# gacyagacya.net
KiCad netlist of a schematic drawn in EAGLE
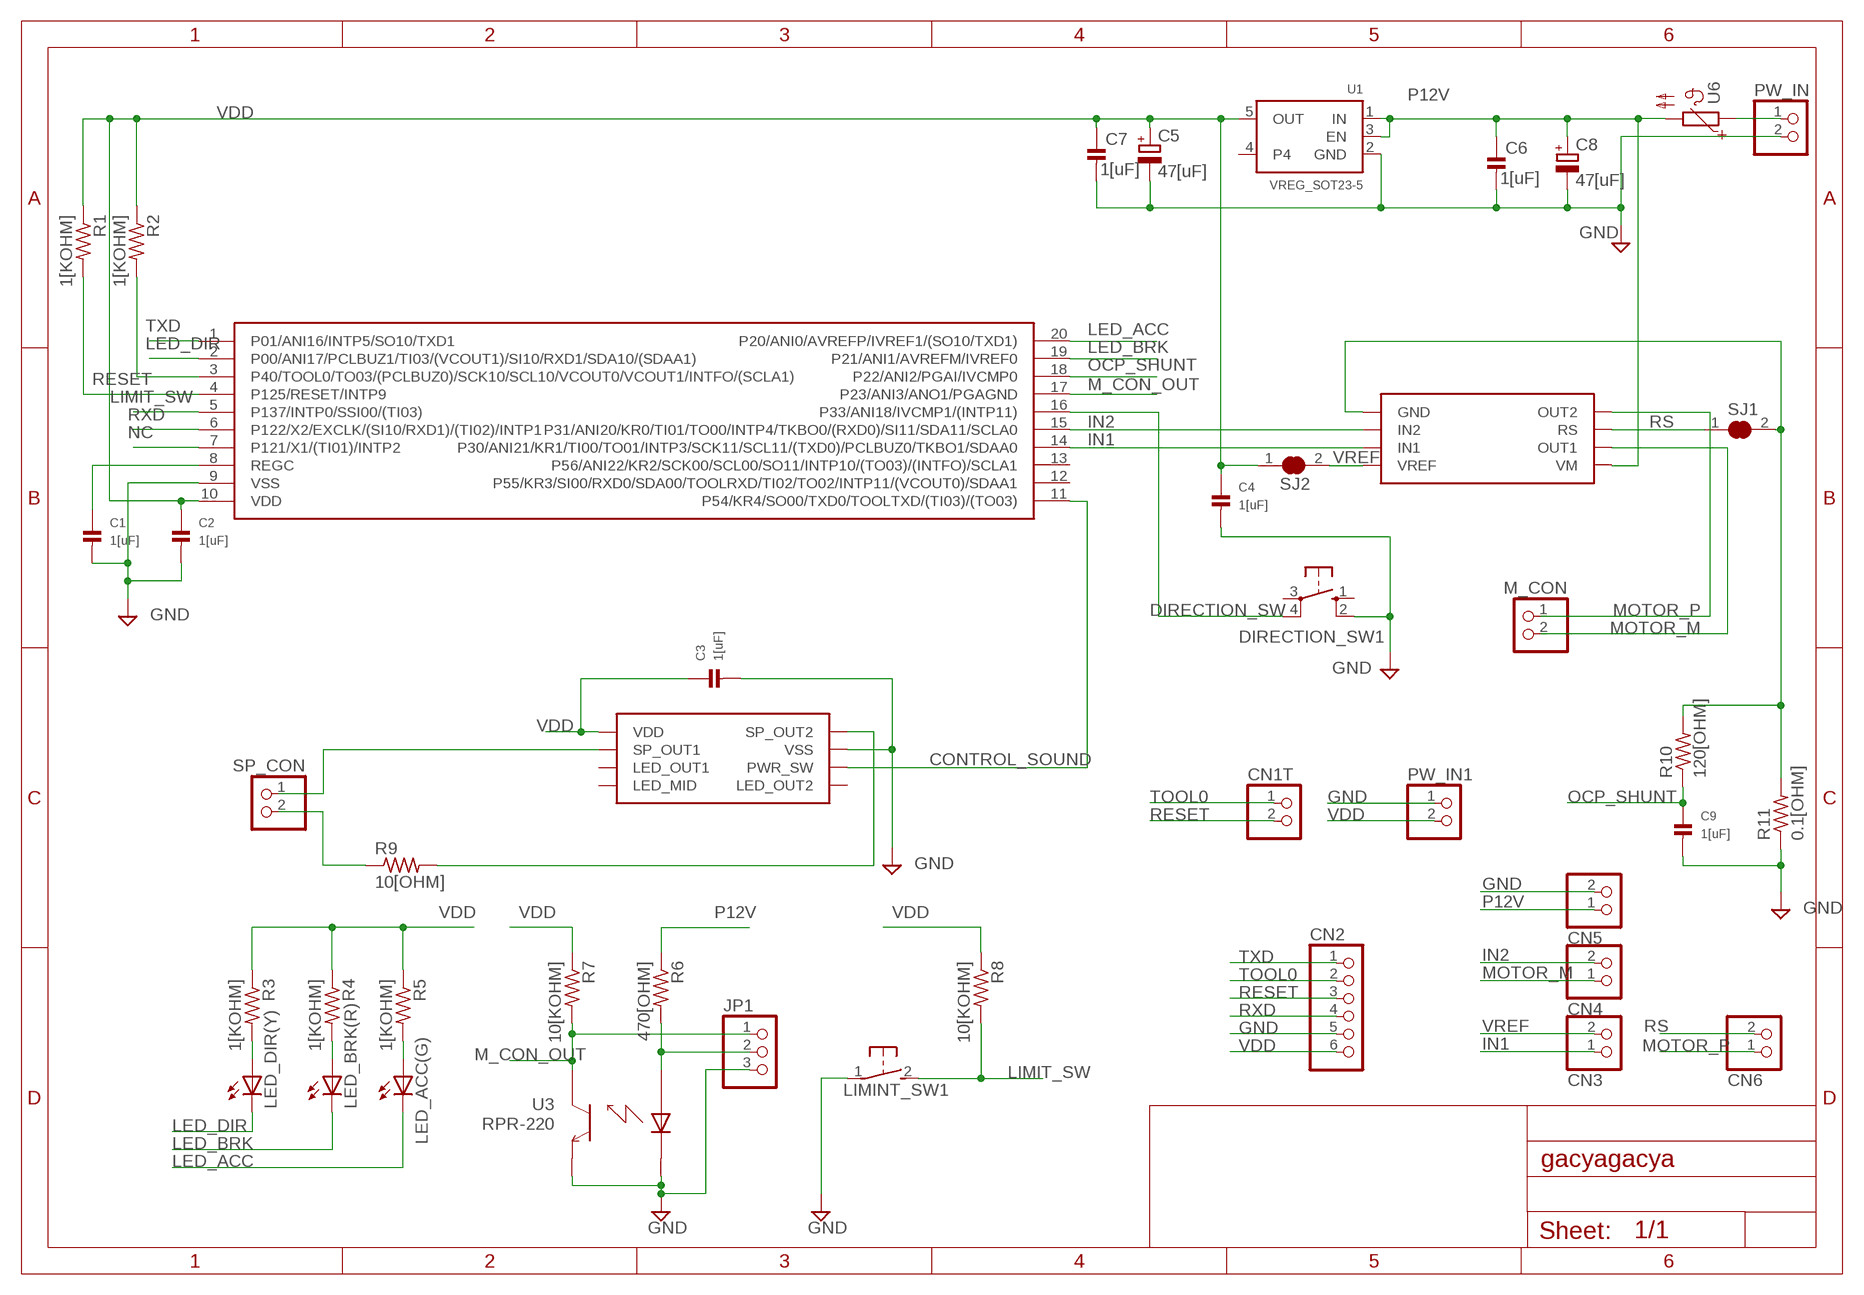
[diagram p0: schematic, sheet 1]

(export (version "E")
  (design (tool "Eeschema 10.0.6"))
  (components
    (comp (ref "C1")
      (value "1[uF]")
      (footprint "eagle-import:_0603")
      (libsource (lib "eagle-import") (part "CAP_CERAMIC_0603"))
    )
    (comp (ref "C2")
      (value "1[uF]")
      (footprint "eagle-import:_0603")
      (libsource (lib "eagle-import") (part "CAP_CERAMIC_0603"))
    )
    (comp (ref "C3")
      (value "1[uF]")
      (footprint "eagle-import:_0603")
      (libsource (lib "eagle-import") (part "CAP_CERAMIC_0603"))
    )
    (comp (ref "C4")
      (value "1[uF]")
      (footprint "eagle-import:_0603")
      (libsource (lib "eagle-import") (part "CAP_CERAMIC_0603"))
    )
    (comp (ref "C5")
      (value "47[uF]")
      (footprint "eagle-import:E1,8-4")
      (libsource (lib "eagle-import") (part "CPOL-EUE1.8-4"))
    )
    (comp (ref "C6")
      (value "1[uF]")
      (footprint "eagle-import:_0603")
      (libsource (lib "eagle-import") (part "CAP_CERAMIC_0603"))
    )
    (comp (ref "C7")
      (value "1[uF]")
      (footprint "eagle-import:_0603")
      (libsource (lib "eagle-import") (part "CAP_CERAMIC_0603"))
    )
    (comp (ref "C8")
      (value "47[uF]")
      (footprint "eagle-import:E1,8-4")
      (libsource (lib "eagle-import") (part "CPOL-EUE1.8-4"))
    )
    (comp (ref "C9")
      (value "1[uF]")
      (footprint "eagle-import:_0603")
      (libsource (lib "eagle-import") (part "CAP_CERAMIC_0603"))
    )
    (comp (ref "CN1T")
      (value "HEADER-1X2ROUND")
      (footprint "eagle-import:1X02_ROUND")
      (libsource (lib "eagle-import") (part "HEADER-1X2ROUND"))
    )
    (comp (ref "CN2")
      (value "XSR_6PIN")
      (footprint "eagle-import:XSR_6PIN")
      (libsource (lib "eagle-import") (part "XSR_6PIN"))
    )
    (comp (ref "CN3")
      (value "HEADER-1X2ROUND")
      (footprint "eagle-import:1X02_ROUND")
      (libsource (lib "eagle-import") (part "HEADER-1X2ROUND"))
    )
    (comp (ref "CN4")
      (value "HEADER-1X2ROUND")
      (footprint "eagle-import:1X02_ROUND")
      (libsource (lib "eagle-import") (part "HEADER-1X2ROUND"))
    )
    (comp (ref "CN5")
      (value "HEADER-1X2ROUND")
      (footprint "eagle-import:1X02_ROUND")
      (libsource (lib "eagle-import") (part "HEADER-1X2ROUND"))
    )
    (comp (ref "CN6")
      (value "HEADER-1X2ROUND")
      (footprint "eagle-import:1X02_ROUND")
      (libsource (lib "eagle-import") (part "HEADER-1X2ROUND"))
    )
    (comp (ref "DIRECTION_SW1")
      (value "10-XXSMD_TACT_SW")
      (footprint "eagle-import:SMD_TACT_SW")
      (libsource (lib "eagle-import") (part "10-XXSMD_TACT_SW"))
    )
    (comp (ref "JP1")
      (value "HEADER-1X3ROUND")
      (footprint "eagle-import:1X03_ROUND")
      (libsource (lib "eagle-import") (part "HEADER-1X3ROUND"))
    )
    (comp (ref "LED_ACC(G)")
      (value "LED3MM")
      (footprint "eagle-import:LED3MM")
      (libsource (lib "eagle-import") (part "LED3MM"))
    )
    (comp (ref "LED_BRK(R)")
      (value "LED3MM")
      (footprint "eagle-import:LED3MM")
      (libsource (lib "eagle-import") (part "LED3MM"))
    )
    (comp (ref "LED_DIR(Y)")
      (value "LED3MM")
      (footprint "eagle-import:LED3MM")
      (libsource (lib "eagle-import") (part "LED3MM"))
    )
    (comp (ref "LIMINT_SW1")
      (value "31-XX")
      (footprint "eagle-import:B3F-31XX")
      (fields (field (name "MPN") "B3F-3100"))
      (libsource (lib "eagle-import") (part "31-XX"))
    )
    (comp (ref "M_CON")
      (value "HEADER-1X2ROUND")
      (footprint "eagle-import:1X02_ROUND")
      (libsource (lib "eagle-import") (part "HEADER-1X2ROUND"))
    )
    (comp (ref "PW_IN")
      (value "HEADER-1X2ROUND")
      (footprint "eagle-import:1X02_ROUND")
      (libsource (lib "eagle-import") (part "HEADER-1X2ROUND"))
    )
    (comp (ref "PW_IN1")
      (value "HEADER-1X2ROUND")
      (footprint "eagle-import:1X02_ROUND")
      (libsource (lib "eagle-import") (part "HEADER-1X2ROUND"))
    )
    (comp (ref "R1")
      (value "1[KOHM]")
      (footprint "eagle-import:R0603")
      (libsource (lib "eagle-import") (part "R-US_R0603"))
    )
    (comp (ref "R2")
      (value "1[KOHM]")
      (footprint "eagle-import:R0603")
      (libsource (lib "eagle-import") (part "R-US_R0603"))
    )
    (comp (ref "R3")
      (value "1[KOHM]")
      (footprint "eagle-import:R0603")
      (libsource (lib "eagle-import") (part "R-US_R0603"))
    )
    (comp (ref "R4")
      (value "1[KOHM]")
      (footprint "eagle-import:R0603")
      (libsource (lib "eagle-import") (part "R-US_R0603"))
    )
    (comp (ref "R5")
      (value "1[KOHM]")
      (footprint "eagle-import:R0603")
      (libsource (lib "eagle-import") (part "R-US_R0603"))
    )
    (comp (ref "R6")
      (value "470[OHM]")
      (footprint "eagle-import:R0603")
      (libsource (lib "eagle-import") (part "R-US_R0603"))
    )
    (comp (ref "R7")
      (value "10[KOHM]")
      (footprint "eagle-import:R0603")
      (libsource (lib "eagle-import") (part "R-US_R0603"))
    )
    (comp (ref "R8")
      (value "10[KOHM]")
      (footprint "eagle-import:R0603")
      (libsource (lib "eagle-import") (part "R-US_R0603"))
    )
    (comp (ref "R9")
      (value "10[OHM]")
      (footprint "eagle-import:R0603")
      (libsource (lib "eagle-import") (part "R-US_R0603"))
    )
    (comp (ref "R10")
      (value "120[OHM]")
      (footprint "eagle-import:R0603")
      (libsource (lib "eagle-import") (part "R-US_R0603"))
    )
    (comp (ref "R11")
      (value "0.1[OHM]")
      (footprint "eagle-import:R0603")
      (libsource (lib "eagle-import") (part "R-US_R0603"))
    )
    (comp (ref "SJ1")
      (value "SOLDERJUMPER_CLOSEDPERM")
      (footprint "eagle-import:SOLDERJUMPER_CLOSEDPERM")
      (libsource (lib "eagle-import") (part "SOLDERJUMPER_CLOSEDPERM"))
    )
    (comp (ref "SJ2")
      (value "SOLDERJUMPER_CLOSEDPERM")
      (footprint "eagle-import:SOLDERJUMPER_CLOSEDPERM")
      (libsource (lib "eagle-import") (part "SOLDERJUMPER_CLOSEDPERM"))
    )
    (comp (ref "SP_CON")
      (value "HEADER-1X2ROUND")
      (footprint "eagle-import:1X02_ROUND")
      (libsource (lib "eagle-import") (part "HEADER-1X2ROUND"))
    )
    (comp (ref "U1")
      (value "VREG_SOT23-5")
      (footprint "eagle-import:SOT23-5")
      (libsource (lib "eagle-import") (part "VREG_SOT23-5"))
    )
    (comp (ref "U2")
      (value "RL78/G11_SSOP20")
      (footprint "eagle-import:SSOP20_225MIL")
      (libsource (lib "eagle-import") (part "RL78/G11_SSOP20"))
    )
    (comp (ref "U3")
      (value "RPR-220")
      (footprint "eagle-import:RPR-220_FOOT_PRINT")
      (libsource (lib "eagle-import") (part "RPR-220"))
    )
    (comp (ref "U4")
      (value "TB67H450FNG")
      (footprint "eagle-import:SOP8")
      (libsource (lib "eagle-import") (part "TB67H450FNG"))
    )
    (comp (ref "U5")
      (value "SOUND_IC_FOR_TETSUKON_GACYA")
      (footprint "eagle-import:SOUND_IC_FOR_TETSUKON_GACYA")
      (libsource (lib "eagle-import") (part "SOUND_IC_FOR_TETSUKON_GACYA"))
    )
    (comp (ref "U6")
      (value "RESETTABLE-PTC-5MM")
      (footprint "eagle-import:DIP_5MM")
      (libsource (lib "eagle-import") (part "RESETTABLE-PTC-5MM"))
    )
  )
  (nets
    (net (code "1") (name "/CONTROL_SOUND") (class "Default")
      (node (ref "U2") (pin "11") (pinfunction "P54/KR4/SO00/TXD0/TOOLTXD/(TI03)/(TO03)_11") (pintype "bidirectional"))
      (node (ref "U5") (pin "6") (pinfunction "PWR_SW_6") (pintype "input"))
    )
    (net (code "2") (name "/DIRECTION_SW") (class "Default")
      (node (ref "DIRECTION_SW1") (pin "4") (pinfunction "P1_4") (pintype "passive"))
      (node (ref "U2") (pin "16") (pinfunction "P33/ANI18/IVCMP1/(INTP11)_16") (pintype "bidirectional"))
    )
    (net (code "3") (name "/IN1") (class "Default")
      (node (ref "CN3") (pin "1") (pinfunction "1_1") (pintype "passive"))
      (node (ref "U2") (pin "14") (pinfunction "P30/ANI21/KR1/TI00/TO01/INTP3/SCK11/SCL11/(TXD0)/PCLBUZ0/TKBO1/SDAA0_14") (pintype "bidirectional"))
      (node (ref "U4") (pin "3") (pinfunction "IN1_3") (pintype "bidirectional"))
    )
    (net (code "4") (name "/IN2") (class "Default")
      (node (ref "CN4") (pin "2") (pinfunction "2_2") (pintype "passive"))
      (node (ref "U2") (pin "15") (pinfunction "P31/ANI20/KR0/TI01/TO00/INTP4/TKBO0/(RXD0)/SI11/SDA11/SCLA0_15") (pintype "bidirectional"))
      (node (ref "U4") (pin "2") (pinfunction "IN2_2") (pintype "input"))
    )
    (net (code "5") (name "/LED_ACC") (class "Default")
      (node (ref "LED_ACC(G)") (pin "K") (pinfunction "C_K") (pintype "passive"))
      (node (ref "U2") (pin "20") (pinfunction "P20/ANI0/AVREFP/IVREF1/(SO10/TXD1)_20") (pintype "bidirectional"))
    )
    (net (code "6") (name "/LED_BRK") (class "Default")
      (node (ref "LED_BRK(R)") (pin "K") (pinfunction "C_K") (pintype "passive"))
      (node (ref "U2") (pin "19") (pinfunction "P21/ANI1/AVREFM/IVREF0_19") (pintype "bidirectional"))
    )
    (net (code "7") (name "/LED_DIR") (class "Default")
      (node (ref "LED_DIR(Y)") (pin "K") (pinfunction "C_K") (pintype "passive"))
      (node (ref "U2") (pin "2") (pinfunction "P00/ANI17/PCLBUZ1/TI03/(VCOUT1)/SI10/RXD1/SDA10/(SDAA1)_2") (pintype "bidirectional"))
    )
    (net (code "8") (name "/LIMIT_SW") (class "Default")
      (node (ref "LIMINT_SW1") (pin "2") (pinfunction "S_2") (pintype "passive"))
      (node (ref "R8") (pin "2") (pinfunction "2_2") (pintype "passive"))
      (node (ref "U2") (pin "5") (pinfunction "P137/INTP0/SSI00/(TI03)_5") (pintype "bidirectional"))
    )
    (net (code "9") (name "/MOTOR_M") (class "Default")
      (node (ref "CN4") (pin "1") (pinfunction "1_1") (pintype "passive"))
      (node (ref "M_CON") (pin "2") (pinfunction "2_2") (pintype "passive"))
      (node (ref "U4") (pin "6") (pinfunction "OUT1_6") (pintype "output"))
    )
    (net (code "10") (name "/MOTOR_P") (class "Default")
      (node (ref "CN6") (pin "1") (pinfunction "1_1") (pintype "passive"))
      (node (ref "M_CON") (pin "1") (pinfunction "1_1") (pintype "passive"))
      (node (ref "U4") (pin "8") (pinfunction "OUT2_8") (pintype "output"))
    )
    (net (code "11") (name "/M_CON_OUT") (class "Default")
      (node (ref "JP1") (pin "1") (pinfunction "1_1") (pintype "passive"))
      (node (ref "R7") (pin "2") (pinfunction "2_2") (pintype "passive"))
      (node (ref "U2") (pin "17") (pinfunction "P23/ANI3/ANO1/PGAGND_17") (pintype "bidirectional"))
      (node (ref "U3") (pin "P$4") (pinfunction "P$4_P$4") (pintype "passive"))
    )
    (net (code "12") (name "/NC") (class "Default")
      (node (ref "U2") (pin "7") (pinfunction "P121/X1/(TI01)/INTP2_7") (pintype "bidirectional"))
    )
    (net (code "13") (name "/OCP_SHUNT") (class "Default")
      (node (ref "C9") (pin "1") (pinfunction "P$1_1") (pintype "passive"))
      (node (ref "R10") (pin "1") (pinfunction "1_1") (pintype "passive"))
      (node (ref "U2") (pin "18") (pinfunction "P22/ANI2/PGAI/IVCMP0_18") (pintype "bidirectional"))
    )
    (net (code "14") (name "/P12V") (class "Default")
      (node (ref "C6") (pin "1") (pinfunction "P$1_1") (pintype "passive"))
      (node (ref "C8") (pin "+") (pinfunction "+_+") (pintype "passive"))
      (node (ref "CN5") (pin "1") (pinfunction "1_1") (pintype "passive"))
      (node (ref "R6") (pin "1") (pinfunction "1_1") (pintype "passive"))
      (node (ref "U1") (pin "1") (pinfunction "IN_1") (pintype "bidirectional"))
      (node (ref "U1") (pin "3") (pinfunction "EN_3") (pintype "bidirectional"))
      (node (ref "U4") (pin "5") (pinfunction "VM_5") (pintype "power_in"))
      (node (ref "U6") (pin "2") (pinfunction "2_2") (pintype "passive"))
    )
    (net (code "15") (name "/RESET") (class "Default")
      (node (ref "CN1T") (pin "2") (pinfunction "2_2") (pintype "passive"))
      (node (ref "CN2") (pin "3") (pinfunction "3_3") (pintype "passive"))
      (node (ref "R1") (pin "2") (pinfunction "2_2") (pintype "passive"))
      (node (ref "U2") (pin "4") (pinfunction "P125/RESET/INTP9_4") (pintype "bidirectional"))
    )
    (net (code "16") (name "/RS") (class "Default")
      (node (ref "CN6") (pin "2") (pinfunction "2_2") (pintype "passive"))
      (node (ref "SJ1") (pin "1") (pinfunction "1_1") (pintype "passive"))
      (node (ref "U4") (pin "7") (pinfunction "RS_7") (pintype "bidirectional"))
    )
    (net (code "17") (name "/RXD") (class "Default")
      (node (ref "CN2") (pin "4") (pinfunction "4_4") (pintype "passive"))
      (node (ref "U2") (pin "6") (pinfunction "P122/X2/EXCLK/(SI10/RXD1)/(TI02)/INTP1_6") (pintype "bidirectional"))
    )
    (net (code "18") (name "/TOOL0") (class "Default")
      (node (ref "CN1T") (pin "1") (pinfunction "1_1") (pintype "passive"))
      (node (ref "CN2") (pin "2") (pinfunction "2_2") (pintype "passive"))
      (node (ref "R2") (pin "2") (pinfunction "2_2") (pintype "passive"))
      (node (ref "U2") (pin "3") (pinfunction "P40/TOOL0/TO03/(PCLBUZ0)/SCK10/SCL10/VCOUT0/VCOUT1/INTFO/(SCLA1)_3") (pintype "bidirectional"))
    )
    (net (code "19") (name "/TXD") (class "Default")
      (node (ref "CN2") (pin "1") (pinfunction "1_1") (pintype "passive"))
      (node (ref "U2") (pin "1") (pinfunction "P01/ANI16/INTP5/SO10/TXD1_1") (pintype "bidirectional"))
    )
    (net (code "20") (name "/VDD") (class "Default")
      (node (ref "C2") (pin "1") (pinfunction "P$1_1") (pintype "passive"))
      (node (ref "C3") (pin "1") (pinfunction "P$1_1") (pintype "passive"))
      (node (ref "C4") (pin "1") (pinfunction "P$1_1") (pintype "passive"))
      (node (ref "C5") (pin "+") (pinfunction "+_+") (pintype "passive"))
      (node (ref "C7") (pin "1") (pinfunction "P$1_1") (pintype "passive"))
      (node (ref "CN2") (pin "6") (pinfunction "6_6") (pintype "passive"))
      (node (ref "PW_IN1") (pin "2") (pinfunction "2_2") (pintype "passive"))
      (node (ref "R1") (pin "1") (pinfunction "1_1") (pintype "passive"))
      (node (ref "R2") (pin "1") (pinfunction "1_1") (pintype "passive"))
      (node (ref "R3") (pin "1") (pinfunction "1_1") (pintype "passive"))
      (node (ref "R4") (pin "1") (pinfunction "1_1") (pintype "passive"))
      (node (ref "R5") (pin "1") (pinfunction "1_1") (pintype "passive"))
      (node (ref "R7") (pin "1") (pinfunction "1_1") (pintype "passive"))
      (node (ref "R8") (pin "1") (pinfunction "1_1") (pintype "passive"))
      (node (ref "SJ2") (pin "1") (pinfunction "1_1") (pintype "passive"))
      (node (ref "U1") (pin "5") (pinfunction "OUT_5") (pintype "bidirectional"))
      (node (ref "U2") (pin "10") (pinfunction "VDD_10") (pintype "power_in"))
      (node (ref "U5") (pin "1") (pinfunction "VDD_1") (pintype "power_in"))
    )
    (net (code "21") (name "/VREF") (class "Default")
      (node (ref "CN3") (pin "2") (pinfunction "2_2") (pintype "passive"))
      (node (ref "SJ2") (pin "2") (pinfunction "2_2") (pintype "passive"))
      (node (ref "U4") (pin "4") (pinfunction "VREF_4") (pintype "input"))
    )
    (net (code "22") (name "GND") (class "Default")
      (node (ref "C1") (pin "2") (pinfunction "P$2_2") (pintype "passive"))
      (node (ref "C2") (pin "2") (pinfunction "P$2_2") (pintype "passive"))
      (node (ref "C3") (pin "2") (pinfunction "P$2_2") (pintype "passive"))
      (node (ref "C4") (pin "2") (pinfunction "P$2_2") (pintype "passive"))
      (node (ref "C5") (pin "-") (pinfunction "-_-") (pintype "passive"))
      (node (ref "C6") (pin "2") (pinfunction "P$2_2") (pintype "passive"))
      (node (ref "C7") (pin "2") (pinfunction "P$2_2") (pintype "passive"))
      (node (ref "C8") (pin "-") (pinfunction "-_-") (pintype "passive"))
      (node (ref "C9") (pin "2") (pinfunction "P$2_2") (pintype "passive"))
      (node (ref "CN2") (pin "5") (pinfunction "5_5") (pintype "passive"))
      (node (ref "CN5") (pin "2") (pinfunction "2_2") (pintype "passive"))
      (node (ref "DIRECTION_SW1") (pin "2") (pinfunction "S1_2") (pintype "passive"))
      (node (ref "JP1") (pin "3") (pinfunction "3_3") (pintype "passive"))
      (node (ref "LIMINT_SW1") (pin "1") (pinfunction "P_1") (pintype "passive"))
      (node (ref "PW_IN") (pin "2") (pinfunction "2_2") (pintype "passive"))
      (node (ref "PW_IN1") (pin "1") (pinfunction "1_1") (pintype "passive"))
      (node (ref "R11") (pin "1") (pinfunction "1_1") (pintype "passive"))
      (node (ref "U1") (pin "2") (pinfunction "GND_2") (pintype "bidirectional"))
      (node (ref "U2") (pin "9") (pinfunction "VSS_9") (pintype "power_in"))
      (node (ref "U3") (pin "P$2") (pinfunction "P$2_P$2") (pintype "passive"))
      (node (ref "U3") (pin "P$3") (pinfunction "P$3_P$3") (pintype "passive"))
      (node (ref "U5") (pin "7") (pinfunction "VSS_7") (pintype "power_in"))
    )
    (net (code "23") (name "Net-(C1-P$1)") (class "Default")
      (node (ref "C1") (pin "1") (pinfunction "P$1_1") (pintype "passive"))
      (node (ref "U2") (pin "8") (pinfunction "REGC_8") (pintype "bidirectional"))
    )
    (net (code "24") (name "Net-(JP1-Pad2)") (class "Default")
      (node (ref "JP1") (pin "2") (pinfunction "2_2") (pintype "passive"))
      (node (ref "R6") (pin "2") (pinfunction "2_2") (pintype "passive"))
      (node (ref "U3") (pin "P$1") (pinfunction "P$1_P$1") (pintype "passive"))
    )
    (net (code "25") (name "Net-(LED_ACC(G)-PadA)") (class "Default")
      (node (ref "LED_ACC(G)") (pin "A") (pinfunction "A_A") (pintype "passive"))
      (node (ref "R5") (pin "2") (pinfunction "2_2") (pintype "passive"))
    )
    (net (code "26") (name "Net-(LED_BRK(R)-PadA)") (class "Default")
      (node (ref "LED_BRK(R)") (pin "A") (pinfunction "A_A") (pintype "passive"))
      (node (ref "R4") (pin "2") (pinfunction "2_2") (pintype "passive"))
    )
    (net (code "27") (name "Net-(LED_DIR(Y)-PadA)") (class "Default")
      (node (ref "LED_DIR(Y)") (pin "A") (pinfunction "A_A") (pintype "passive"))
      (node (ref "R3") (pin "2") (pinfunction "2_2") (pintype "passive"))
    )
    (net (code "28") (name "Net-(PW_IN-Pad1)") (class "Default")
      (node (ref "PW_IN") (pin "1") (pinfunction "1_1") (pintype "passive"))
      (node (ref "U6") (pin "1") (pinfunction "1_1") (pintype "passive"))
    )
    (net (code "29") (name "Net-(R9-Pad1)") (class "Default")
      (node (ref "R9") (pin "1") (pinfunction "1_1") (pintype "passive"))
      (node (ref "SP_CON") (pin "2") (pinfunction "2_2") (pintype "passive"))
    )
    (net (code "30") (name "Net-(U4-GND)") (class "Default")
      (node (ref "R10") (pin "2") (pinfunction "2_2") (pintype "passive"))
      (node (ref "R11") (pin "2") (pinfunction "2_2") (pintype "passive"))
      (node (ref "SJ1") (pin "2") (pinfunction "2_2") (pintype "passive"))
      (node (ref "U4") (pin "1") (pinfunction "GND_1") (pintype "power_in"))
    )
    (net (code "31") (name "Net-(U5-SP_OUT1)") (class "Default")
      (node (ref "SP_CON") (pin "1") (pinfunction "1_1") (pintype "passive"))
      (node (ref "U5") (pin "2") (pinfunction "SP_OUT1_2") (pintype "output"))
    )
    (net (code "32") (name "Net-(U5-SP_OUT2)") (class "Default")
      (node (ref "R9") (pin "2") (pinfunction "2_2") (pintype "passive"))
      (node (ref "U5") (pin "8") (pinfunction "SP_OUT2_8") (pintype "output"))
    )
    (net (code "33") (name "unconnected-(DIRECTION_SW1-P-Pad3)") (class "Default")
      (node (ref "DIRECTION_SW1") (pin "3") (pinfunction "P_3") (pintype "passive"))
    )
    (net (code "34") (name "unconnected-(DIRECTION_SW1-S-Pad1)") (class "Default")
      (node (ref "DIRECTION_SW1") (pin "1") (pinfunction "S_1") (pintype "passive"))
    )
    (net (code "35") (name "unconnected-(U1-P4-Pad4)") (class "Default")
      (node (ref "U1") (pin "4") (pinfunction "P4_4") (pintype "bidirectional"))
    )
    (net (code "36") (name "unconnected-(U2-P55{slash}KR3{slash}SI00{slash}RXD0{slash}SDA00{slash}TOOLRXD{slash}TI02{slash}TO02{slash}INTP11{slash}(VCOUT0){slash}SDAA1-Pad12)") (class "Default")
      (node (ref "U2") (pin "12") (pinfunction "P55/KR3/SI00/RXD0/SDA00/TOOLRXD/TI02/TO02/INTP11/(VCOUT0)/SDAA1_12") (pintype "bidirectional"))
    )
    (net (code "37") (name "unconnected-(U2-P56{slash}ANI22{slash}KR2{slash}SCK00{slash}SCL00{slash}SO11{slash}INTP10{slash}(TO03){slash}(INTFO){slash}SCLA1-Pad13)") (class "Default")
      (node (ref "U2") (pin "13") (pinfunction "P56/ANI22/KR2/SCK00/SCL00/SO11/INTP10/(TO03)/(INTFO)/SCLA1_13") (pintype "bidirectional"))
    )
    (net (code "38") (name "unconnected-(U5-LED_MID-Pad4)") (class "Default")
      (node (ref "U5") (pin "4") (pinfunction "LED_MID_4") (pintype "bidirectional"))
    )
    (net (code "39") (name "unconnected-(U5-LED_OUT1-Pad3)") (class "Default")
      (node (ref "U5") (pin "3") (pinfunction "LED_OUT1_3") (pintype "bidirectional"))
    )
    (net (code "40") (name "unconnected-(U5-LED_OUT2-Pad5)") (class "Default")
      (node (ref "U5") (pin "5") (pinfunction "LED_OUT2_5") (pintype "bidirectional"))
    )
  )
)
